# ESP8266.net
KiCad netlist of a schematic drawn in Altium Designer
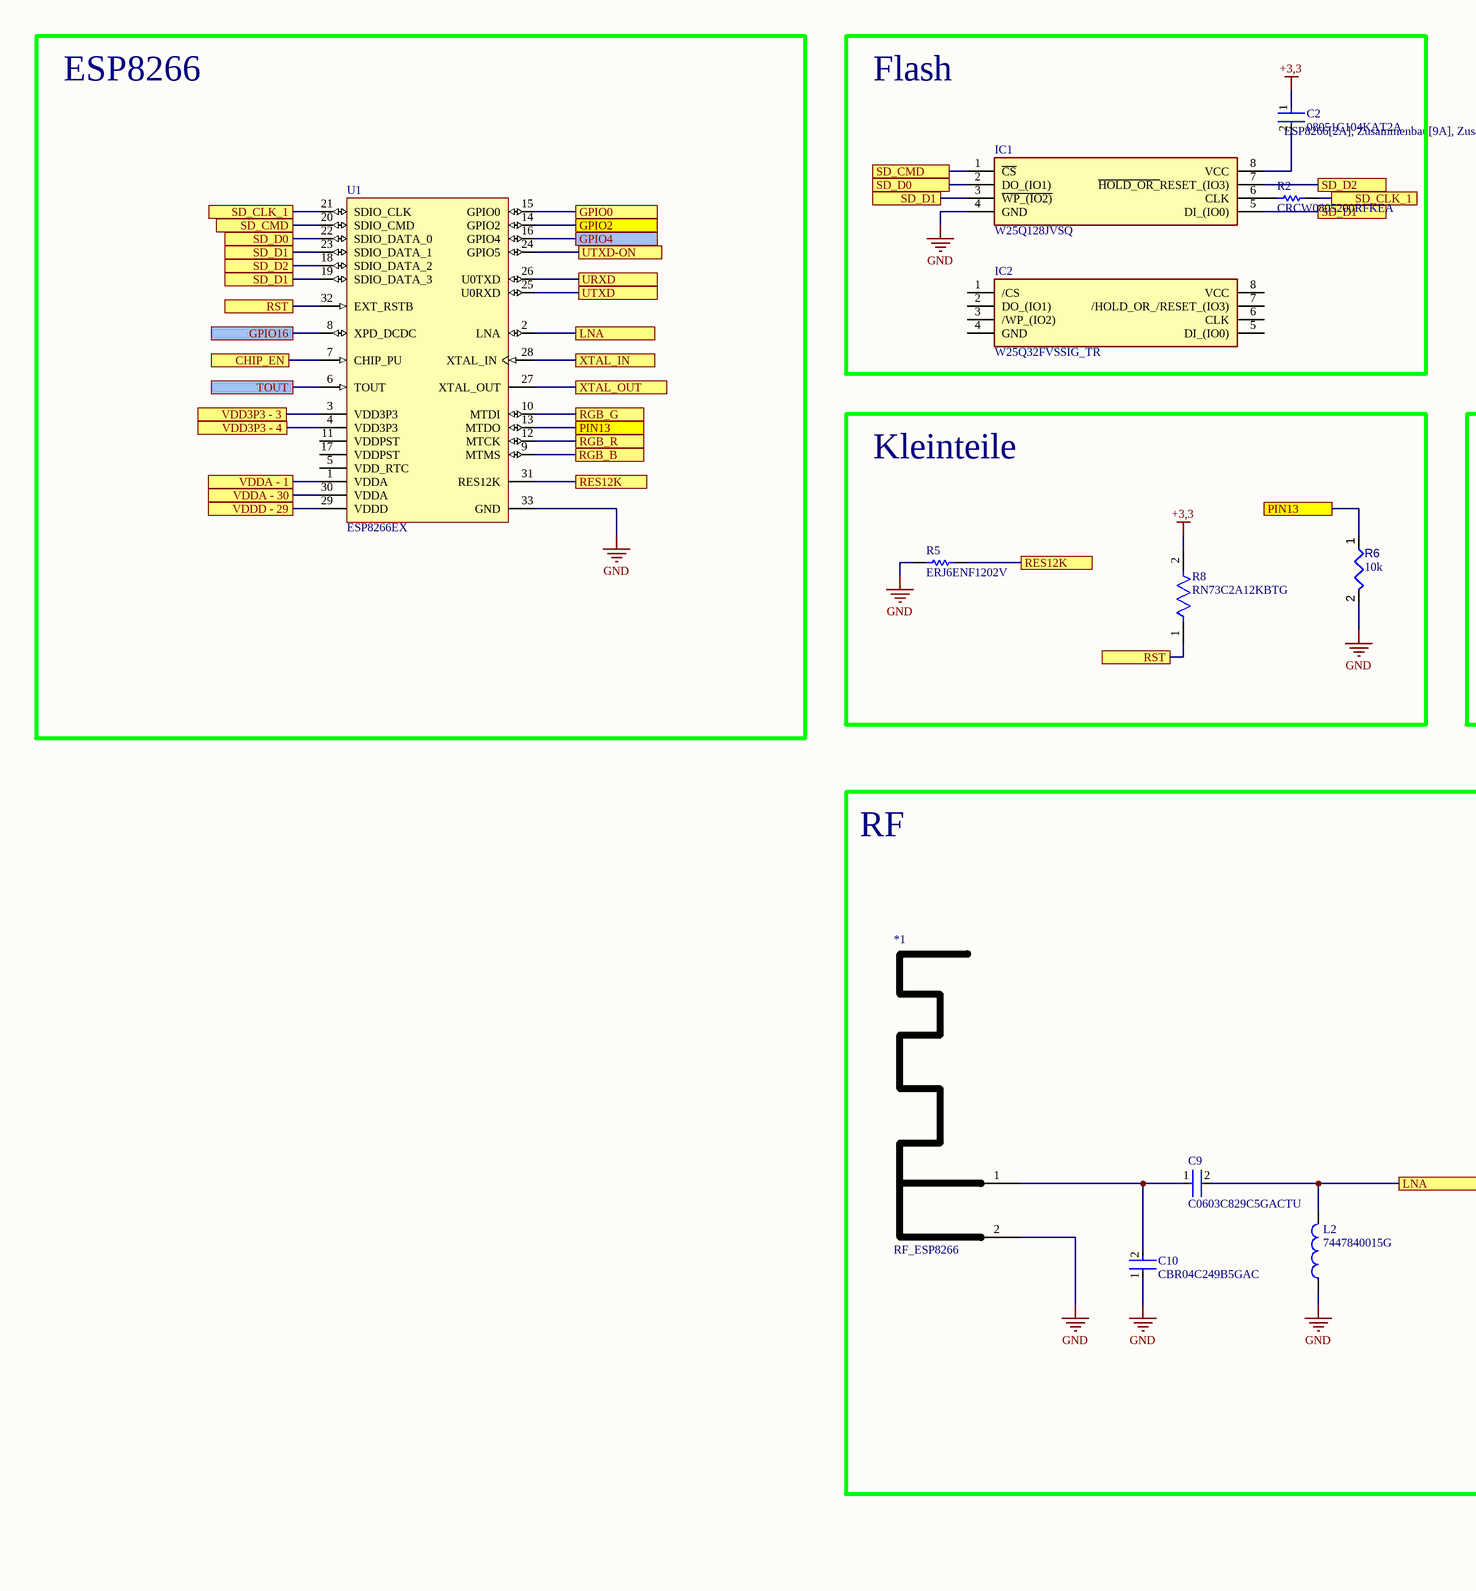
[diagram p0: ESP8266.SchDoc, left]
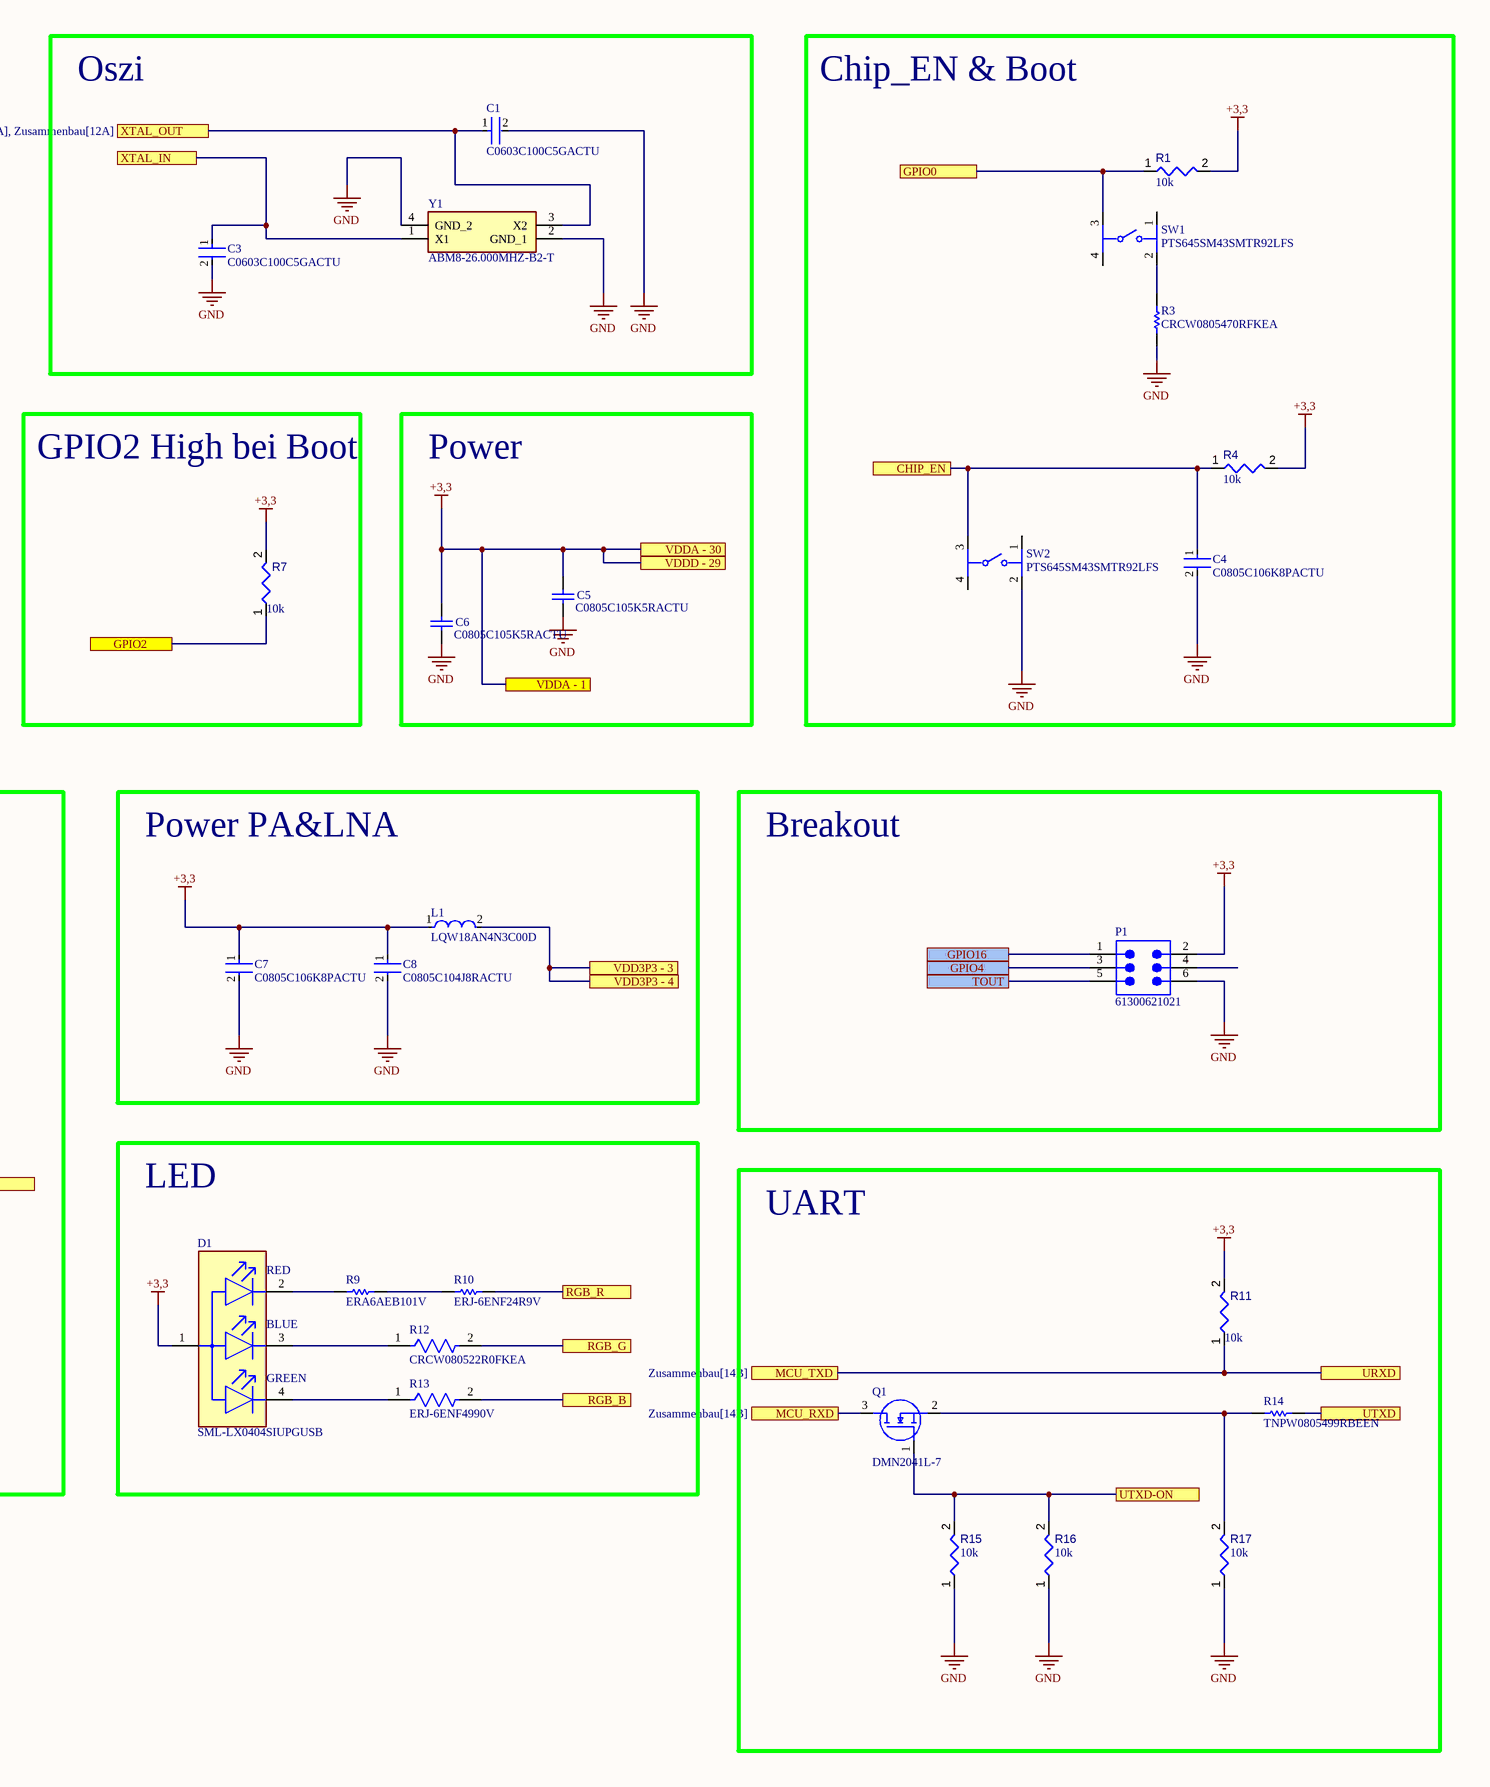
[diagram p1: ESP8266.SchDoc, right]

(export (version "E")
  (design (tool "Eeschema 10.0.6"))
  (components
    (comp (ref "*1")
      (value "RF_ESP8266")
      (footprint "PCBComponent_1")
      (libsource (lib "Stefan Hörtnagl") (part "Component_1"))
    )
    (comp (ref "C1")
      (value "C0603C100C5GACTU")
      (footprint "FP-C0603C-CF-MFG")
      (description "CAP CER 10PF 50V NP0 0603")
      (fields (field (name "MANUFACTURER") "KEMET") (field (name "TOLERANCE") "0.25 pF"))
      (libsource (lib "Altium Content Vault") (part "b4654b650e69147ec39a6b967a45e02"))
    )
    (comp (ref "C2")
      (value "08051C104KAT2A")
      (footprint "FP-0805-L_2_01_0_2-W_1_25-IPC_B")
      (description "General Purpose Ceramic Capacitor, 0805, 100nF, 10%, X7R, 15%, 100V")
      (fields (field (name "VOLTAGE") "100V") (field (name "TOLERANCE") "10%"))
      (libsource (lib "Altium Content Vault") (part "b4654b650e69147ec39a6b967a45e02"))
    )
    (comp (ref "C3")
      (value "C0603C100C5GACTU")
      (footprint "FP-C0603C-CF-MFG")
      (description "CAP CER 10PF 50V NP0 0603")
      (fields (field (name "MANUFACTURER") "KEMET") (field (name "TOLERANCE") "0.25 pF"))
      (libsource (lib "Altium Content Vault") (part "b4654b650e69147ec39a6b967a45e02"))
    )
    (comp (ref "C4")
      (value "C0805C106K8PACTU")
      (footprint "FP-C0805C-DG-MFG")
      (description "CAP CER 10UF 10V X5R 0805")
      (fields (field (name "TOLERANCE") "10%") (field (name "MANUFACTURER") "Kemet"))
      (libsource (lib "Altium Content Vault") (part "11868f565c42a9108669ba33697ecf6"))
    )
    (comp (ref "C5")
      (value "C0805C105K5RACTU")
      (footprint "CAPC2013X140X50ML20T25")
      (fields (field (name "MANUFACTURER") "Kemet"))
      (libsource (lib "Altium Content Vault") (part "CAP"))
    )
    (comp (ref "C6")
      (value "C0805C105K5RACTU")
      (footprint "CAPC2013X140X50ML20T25")
      (fields (field (name "MANUFACTURER") "Kemet"))
      (libsource (lib "Altium Content Vault") (part "CAP"))
    )
    (comp (ref "C7")
      (value "C0805C106K8PACTU")
      (footprint "FP-C0805C-DG-MFG")
      (description "CAP CER 10UF 10V X5R 0805")
      (fields (field (name "TOLERANCE") "10%") (field (name "MANUFACTURER") "Kemet"))
      (libsource (lib "Altium Content Vault") (part "11868f565c42a9108669ba33697ecf6"))
    )
    (comp (ref "C8")
      (value "C0805C104J8RACTU")
      (footprint "FP-C0805C-DN-MFG")
      (description "CAP CER 0.1UF 10V 5% X7R 0805")
      (fields (field (name "MANUFACTURER") "KEMET") (field (name "TOLERANCE") "0.05"))
      (libsource (lib "Altium Content Vault") (part "b4654b650e69147ec39a6b967a45e02"))
    )
    (comp (ref "C9")
      (value "C0603C829C5GACTU")
      (footprint "FP-C0603C-CF-MFG")
      (description "CAP CER 8.2PF 50V NP0 0603")
      (fields
        (field (name "OCTOPART") "https://octopart.com/c0603c829c5gactu-kemet-8375751")
        (field (name "TOLERANCE") "0.25 pF")
      )
      (libsource (lib "Altium Content Vault") (part "b4654b650e69147ec39a6b967a45e02"))
    )
    (comp (ref "C10")
      (value "CBR04C249B5GAC")
      (footprint "FP-CBR04C-MFG")
      (description "CBR0402 2.4 pF 30ppm/°C 0.1 pF C0G 50 V")
      (fields
        (field (name "OCTOPART") "https://octopart.com/cbr04c249b5gac-kemet-75200062")
        (field (name "MANUFACTURER") "KEMET")
      )
      (libsource (lib "Altium Content Vault") (part "236180d848d6139a670b325ea6854c9"))
    )
    (comp (ref "D1")
      (value "SML-LX0404SIUPGUSB")
      (footprint "FP-SML-LX0404SIUPGUSB-MFG")
      (description "LED RGB CLEAR SMD")
      (libsource (lib "Altium Content Vault") (part "2e8871f6955a40d35a6a753e53ead77"))
    )
    (comp (ref "IC1")
      (value "W25Q128JVSQ")
      (footprint "SamacSys:SOIC127P790X216-8N")
      (description "Integrated Circuit")
      (libsource (lib "*") (part "W25Q128JVSQ"))
    )
    (comp (ref "IC2")
      (value "W25Q32FVSSIG_TR")
      (footprint "SamacSys:SOIC127P790X216-8N")
      (description "Integrated Circuit")
      (fields (field (name "MANUFACTURER_PART_NUMBER") "W25Q32FVSSIG TR"))
      (libsource (lib "*") (part "W25Q32FVSSIG_TR"))
    )
    (comp (ref "L1")
      (value "LQW18AN4N3C00D")
      (footprint "FP-LQW18AN_00-MFG")
      (description "Wire Wound RF Inductor 4.3nH ±0.2nH 850mA 0.059Ω 0603 (1608)")
      (libsource (lib "Altium Content Vault") (part "725321dda6339637d4d059423bc1c3c"))
    )
    (comp (ref "L2")
      (value "7447840015G")
      (footprint "WE-MK_0402_L1W0.5H0.5")
      (description "7447840015G Multilayer Inductor, 1.5Nh, 0.3A, 0402 Rohs Compliant: Yes")
      (libsource (lib "Altium Content Vault") (part "Inductor - 1"))
    )
    (comp (ref "P1")
      (value "61300621021")
      (footprint "61300621021")
      (libsource (lib "Altium Content Vault") (part "Header_Male_2R_06P"))
    )
    (comp (ref "Q1")
      (value "DMN2041L-7")
      (footprint "SamacSys:SOT96P240X110-3N")
      (description "MOSFET (N-Channel)")
      (fields (field (name "MOUSER PART NUMBER") "621-DMN2041L-7"))
      (libsource (lib "*") (part "DMN2041L-7"))
    )
    (comp (ref "R1")
      (value "10k")
      (footprint "RESC2013X50X35ML15T15")
      (description "Chip Resistor, 10 KOhm, +/- 1%, 125 mW, -55 to 155 degC, 0805 (2012 Metric)")
      (fields (field (name "TOLERANCE") "1%") (field (name "POWER") "125mW"))
      (libsource (lib "Stefan Hörtnagl") (part "RES-2"))
    )
    (comp (ref "R2")
      (value "CRCW0805200RFKEA")
      (footprint "RESC2013X50X30NL20T20")
      (fields (field (name "MANUFACTURER") "Vishay Dale"))
      (libsource (lib "Altium Content Vault") (part "RES"))
    )
    (comp (ref "R3")
      (value "CRCW0805470RFKEA")
      (footprint "RESC2013X50X30LL20T20")
      (fields (field (name "MANUFACTURER") "Vishay Dale"))
      (libsource (lib "Altium Content Vault") (part "RES"))
    )
    (comp (ref "R4")
      (value "10k")
      (footprint "RESC2013X50X35ML15T15")
      (description "Chip Resistor, 10 KOhm, +/- 1%, 125 mW, -55 to 155 degC, 0805 (2012 Metric)")
      (fields (field (name "TOLERANCE") "1%") (field (name "POWER") "125mW"))
      (libsource (lib "Stefan Hörtnagl") (part "RES-2"))
    )
    (comp (ref "R5")
      (value "ERJ6ENF1202V")
      (footprint "RESC2013X70X40ML20T20")
      (fields (field (name "MANUFACTURER") "Panasonic"))
      (libsource (lib "Altium Content Vault") (part "RES"))
    )
    (comp (ref "R6")
      (value "10k")
      (footprint "RESC2013X50X35ML15T15")
      (description "Chip Resistor, 10 KOhm, +/- 1%, 125 mW, -55 to 155 degC, 0805 (2012 Metric)")
      (fields (field (name "TOLERANCE") "1%") (field (name "POWER") "125mW"))
      (libsource (lib "Stefan Hörtnagl") (part "RES-2"))
    )
    (comp (ref "R7")
      (value "10k")
      (footprint "RESC2013X50X35ML15T15")
      (description "Chip Resistor, 10 KOhm, +/- 1%, 125 mW, -55 to 155 degC, 0805 (2012 Metric)")
      (fields (field (name "TOLERANCE") "1%") (field (name "POWER") "125mW"))
      (libsource (lib "Stefan Hörtnagl") (part "RES-2"))
    )
    (comp (ref "R8")
      (value "RN73C2A12KBTG")
      (footprint "FP-RN732A-MFG")
      (description "SMD Chip Resistor, Thin Film, 12KΩ, 100 V, 0805 [2012 Metric], 100 mW, 0.1%, RN73 Series")
      (fields (field (name "TOLERANCE") "0.1%") (field (name "MANUFACTURER") "TE Connectivity"))
      (libsource (lib "Altium Content Vault") (part "1029c3af85768c4190bb7ad29bc67b5"))
    )
    (comp (ref "R9")
      (value "ERA6AEB101V")
      (footprint "RESC2013X60X40ML20T25")
      (fields (field (name "MANUFACTURER") "Panasonic"))
      (libsource (lib "Altium Content Vault") (part "RES"))
    )
    (comp (ref "R10")
      (value "ERJ-6ENF24R9V")
      (footprint "RESC2013X70X40ML20T20")
      (fields (field (name "MANUFACTURER") "Panasonic"))
      (libsource (lib "Altium Content Vault") (part "RES"))
    )
    (comp (ref "R11")
      (value "10k")
      (footprint "RESC2013X50X35ML15T15")
      (description "Chip Resistor, 10 KOhm, +/- 1%, 125 mW, -55 to 155 degC, 0805 (2012 Metric)")
      (fields (field (name "TOLERANCE") "1%") (field (name "POWER") "125mW"))
      (libsource (lib "Stefan Hörtnagl") (part "RES-2"))
    )
    (comp (ref "R12")
      (value "CRCW080522R0FKEA")
      (footprint "FP-CRCW0805-e3-IPC_C")
      (description "RES Thick Film, 22Ω, 1%, 0.125W, 100ppm/°C, 0805")
      (fields (field (name "TOLERANCE") "1%"))
      (libsource (lib "Altium Content Vault") (part "1029c3af85768c4190bb7ad29bc67b5"))
    )
    (comp (ref "R13")
      (value "ERJ-6ENF4990V")
      (footprint "FP-ERJ6EN-IPC_B")
      (description "RES SMD 499 OHM 1% 1/8W 0805")
      (fields (field (name "TOLERANCE") "1%"))
      (libsource (lib "Altium Content Vault") (part "1029c3af85768c4190bb7ad29bc67b5"))
    )
    (comp (ref "R14")
      (value "TNPW0805499RBEEN")
      (footprint "RESC2013X55X40NL15T20")
      (fields (field (name "MANUFACTURER") "Vishay Dale"))
      (libsource (lib "Altium Content Vault") (part "RES"))
    )
    (comp (ref "R15")
      (value "10k")
      (footprint "RESC2013X50X35ML15T15")
      (description "Chip Resistor, 10 KOhm, +/- 1%, 125 mW, -55 to 155 degC, 0805 (2012 Metric)")
      (fields (field (name "TOLERANCE") "1%") (field (name "POWER") "125mW"))
      (libsource (lib "Stefan Hörtnagl") (part "RES-2"))
    )
    (comp (ref "R16")
      (value "10k")
      (footprint "RESC2013X50X35ML15T15")
      (description "Chip Resistor, 10 KOhm, +/- 1%, 125 mW, -55 to 155 degC, 0805 (2012 Metric)")
      (fields (field (name "TOLERANCE") "1%") (field (name "POWER") "125mW"))
      (libsource (lib "Stefan Hörtnagl") (part "RES-2"))
    )
    (comp (ref "R17")
      (value "10k")
      (footprint "RESC2013X50X35ML15T15")
      (description "Chip Resistor, 10 KOhm, +/- 1%, 125 mW, -55 to 155 degC, 0805 (2012 Metric)")
      (fields (field (name "TOLERANCE") "1%") (field (name "POWER") "125mW"))
      (libsource (lib "Stefan Hörtnagl") (part "RES-2"))
    )
    (comp (ref "SW1")
      (value "PTS645SM43SMTR92LFS")
      (footprint "FP-PTS645SM43SMTR92LFS-MFG")
      (description "SWITCH TACTILE SPST-NO 0.05A 12V")
      (libsource (lib "Altium Content Vault") (part "1adf0dd01260c80cf25a44bfd6b99ba"))
    )
    (comp (ref "SW2")
      (value "PTS645SM43SMTR92LFS")
      (footprint "FP-PTS645SM43SMTR92LFS-MFG")
      (description "SWITCH TACTILE SPST-NO 0.05A 12V")
      (libsource (lib "Altium Content Vault") (part "1adf0dd01260c80cf25a44bfd6b99ba"))
    )
    (comp (ref "U1")
      (value "ESP8266EX")
      (footprint "ESFS-QFN-32_L")
      (description "Low-Power, Highly-Integrated Wi-Fi Solution, 2.5 to 3.6 V, 80 mA, -40 to 125 degC, 32-Pin QFN")
      (fields (field (name "MANUFACTURER") "Espressif Systems"))
      (libsource (lib "Altium Content Vault") (part "ESFS-ESP8266EX-32"))
    )
    (comp (ref "Y1")
      (value "ABM8-26.000MHZ-B2-T")
      (footprint "SamacSys:ABM810000MHZ12D2W")
      (description "Crystal or Oscillator")
      (libsource (lib "*") (part "ABM8-26.000MHZ-B2-T"))
    )
  )
  (nets
    (net (code "1") (name "+3,3") (class "Default")
      (node (ref "C2") (pin "1") (pinfunction "1_1") (pintype "passive"))
      (node (ref "C5") (pin "2") (pinfunction "2_2") (pintype "passive"))
      (node (ref "C6") (pin "2") (pinfunction "2_2") (pintype "passive"))
      (node (ref "C7") (pin "1") (pinfunction "1_1") (pintype "passive"))
      (node (ref "C8") (pin "1") (pinfunction "1_1") (pintype "passive"))
      (node (ref "D1") (pin "1") (pinfunction "Common_Anode_1") (pintype "passive"))
      (node (ref "L1") (pin "1") (pinfunction "1_1") (pintype "passive"))
      (node (ref "P1") (pin "2") (pinfunction "2_2") (pintype "passive"))
      (node (ref "R1") (pin "2") (pinfunction "2_2") (pintype "passive"))
      (node (ref "R11") (pin "2") (pinfunction "2_2") (pintype "passive"))
      (node (ref "R4") (pin "2") (pinfunction "2_2") (pintype "passive"))
      (node (ref "R7") (pin "2") (pinfunction "2_2") (pintype "passive"))
      (node (ref "R8") (pin "2") (pinfunction "2_2") (pintype "passive"))
      (node (ref "U1") (pin "1") (pinfunction "VDDA_1") (pintype "power_in"))
      (node (ref "U1") (pin "29") (pinfunction "VDDD_29") (pintype "power_in"))
      (node (ref "U1") (pin "30") (pinfunction "VDDA_30") (pintype "power_in"))
    )
    (net (code "2") (name "/CHIP_EN") (class "Default")
      (node (ref "C4") (pin "1") (pinfunction "1_1") (pintype "passive"))
      (node (ref "R4") (pin "1") (pinfunction "1_1") (pintype "passive"))
      (node (ref "SW2") (pin "3") (pinfunction "3_3") (pintype "passive"))
      (node (ref "U1") (pin "7") (pinfunction "CHIP_PU_7") (pintype "input"))
    )
    (net (code "3") (name "/GPIO0") (class "Default")
      (node (ref "R1") (pin "1") (pinfunction "1_1") (pintype "passive"))
      (node (ref "SW1") (pin "3") (pinfunction "3_3") (pintype "passive"))
      (node (ref "U1") (pin "15") (pinfunction "GPIO0_15") (pintype "bidirectional"))
    )
    (net (code "4") (name "/GPIO2") (class "Default")
      (node (ref "R7") (pin "1") (pinfunction "1_1") (pintype "passive"))
      (node (ref "U1") (pin "14") (pinfunction "GPIO2_14") (pintype "bidirectional"))
    )
    (net (code "5") (name "/GPIO4") (class "Default")
      (node (ref "P1") (pin "3") (pinfunction "3_3") (pintype "passive"))
      (node (ref "U1") (pin "16") (pinfunction "GPIO4_16") (pintype "bidirectional"))
    )
    (net (code "6") (name "/GPIO16") (class "Default")
      (node (ref "P1") (pin "1") (pinfunction "1_1") (pintype "passive"))
      (node (ref "U1") (pin "8") (pinfunction "XPD_DCDC_8") (pintype "bidirectional"))
    )
    (net (code "7") (name "/LNA") (class "Default")
      (node (ref "C9") (pin "2") (pinfunction "2_2") (pintype "passive"))
      (node (ref "L2") (pin "2") (pinfunction "2_2") (pintype "passive"))
      (node (ref "U1") (pin "2") (pinfunction "LNA_2") (pintype "bidirectional"))
    )
    (net (code "8") (name "/MCU_RXD") (class "Default")
      (node (ref "Q1") (pin "3") (pinfunction "D_3") (pintype "passive"))
    )
    (net (code "9") (name "/MCU_TXD") (class "Default")
      (node (ref "R11") (pin "1") (pinfunction "1_1") (pintype "passive"))
      (node (ref "U1") (pin "26") (pinfunction "U0TXD_26") (pintype "bidirectional"))
    )
    (net (code "10") (name "/PIN13") (class "Default")
      (node (ref "R6") (pin "1") (pinfunction "1_1") (pintype "passive"))
      (node (ref "U1") (pin "13") (pinfunction "MTDO_13") (pintype "bidirectional"))
    )
    (net (code "11") (name "/RES12K") (class "Default")
      (node (ref "R5") (pin "2") (pinfunction "2_2") (pintype "passive"))
      (node (ref "U1") (pin "31") (pinfunction "RES12K_31") (pintype "passive"))
    )
    (net (code "12") (name "/RGB_B") (class "Default")
      (node (ref "R13") (pin "2") (pinfunction "2_2") (pintype "passive"))
      (node (ref "U1") (pin "9") (pinfunction "MTMS_9") (pintype "bidirectional"))
    )
    (net (code "13") (name "/RGB_G") (class "Default")
      (node (ref "R12") (pin "2") (pinfunction "2_2") (pintype "passive"))
      (node (ref "U1") (pin "10") (pinfunction "MTDI_10") (pintype "bidirectional"))
    )
    (net (code "14") (name "/RGB_R") (class "Default")
      (node (ref "R10") (pin "2") (pinfunction "2_2") (pintype "passive"))
      (node (ref "U1") (pin "12") (pinfunction "MTCK_12") (pintype "bidirectional"))
    )
    (net (code "15") (name "/RST") (class "Default")
      (node (ref "R8") (pin "1") (pinfunction "1_1") (pintype "passive"))
      (node (ref "U1") (pin "32") (pinfunction "EXT_RSTB_32") (pintype "input"))
    )
    (net (code "16") (name "/SD_CLK_1") (class "Default")
      (node (ref "R2") (pin "2") (pinfunction "2_2") (pintype "passive"))
      (node (ref "U1") (pin "21") (pinfunction "SDIO_CLK_21") (pintype "bidirectional"))
    )
    (net (code "17") (name "/SD_CMD") (class "Default")
      (node (ref "IC1") (pin "1") (pinfunction "~{CS}_1") (pintype "passive"))
      (node (ref "U1") (pin "20") (pinfunction "SDIO_CMD_20") (pintype "bidirectional"))
    )
    (net (code "18") (name "/SD_D0") (class "Default")
      (node (ref "IC1") (pin "2") (pinfunction "DO_(IO1)_2") (pintype "passive"))
      (node (ref "U1") (pin "22") (pinfunction "SDIO_DATA_0_22") (pintype "bidirectional"))
    )
    (net (code "19") (name "/SD_D1") (class "Default")
      (node (ref "IC1") (pin "3") (pinfunction "~{WP_(IO2)}_3") (pintype "passive"))
      (node (ref "IC1") (pin "5") (pinfunction "DI_(IO0)_5") (pintype "passive"))
      (node (ref "U1") (pin "19") (pinfunction "SDIO_DATA_3_19") (pintype "bidirectional"))
      (node (ref "U1") (pin "23") (pinfunction "SDIO_DATA_1_23") (pintype "bidirectional"))
    )
    (net (code "20") (name "/SD_D2") (class "Default")
      (node (ref "IC1") (pin "7") (pinfunction "~{HOLD_OR_}RESET_(IO3)_7") (pintype "passive"))
      (node (ref "U1") (pin "18") (pinfunction "SDIO_DATA_2_18") (pintype "bidirectional"))
    )
    (net (code "21") (name "/TOUT") (class "Default")
      (node (ref "P1") (pin "5") (pinfunction "5_5") (pintype "passive"))
      (node (ref "U1") (pin "6") (pinfunction "TOUT_6") (pintype "input"))
    )
    (net (code "22") (name "/UTXD") (class "Default")
      (node (ref "R14") (pin "2") (pinfunction "2_2") (pintype "passive"))
      (node (ref "U1") (pin "25") (pinfunction "U0RXD_25") (pintype "bidirectional"))
    )
    (net (code "23") (name "/UTXD-ON") (class "Default")
      (node (ref "Q1") (pin "1") (pinfunction "G_1") (pintype "passive"))
      (node (ref "R15") (pin "2") (pinfunction "2_2") (pintype "passive"))
      (node (ref "R16") (pin "2") (pinfunction "2_2") (pintype "passive"))
      (node (ref "U1") (pin "24") (pinfunction "GPIO5_24") (pintype "bidirectional"))
    )
    (net (code "24") (name "/VDD3P3 - 3") (class "Default")
      (node (ref "L1") (pin "2") (pinfunction "2_2") (pintype "passive"))
      (node (ref "U1") (pin "3") (pinfunction "VDD3P3_3") (pintype "power_in"))
      (node (ref "U1") (pin "4") (pinfunction "VDD3P3_4") (pintype "power_in"))
    )
    (net (code "25") (name "/XTAL_IN") (class "Default")
      (node (ref "C3") (pin "1") (pinfunction "1_1") (pintype "passive"))
      (node (ref "U1") (pin "28") (pinfunction "XTAL_IN_28") (pintype "input"))
      (node (ref "Y1") (pin "1") (pinfunction "X1_1") (pintype "passive"))
    )
    (net (code "26") (name "/XTAL_OUT") (class "Default")
      (node (ref "C1") (pin "1") (pinfunction "1_1") (pintype "passive"))
      (node (ref "U1") (pin "27") (pinfunction "XTAL_OUT_27") (pintype "passive"))
      (node (ref "Y1") (pin "3") (pinfunction "X2_3") (pintype "passive"))
    )
    (net (code "27") (name "GND") (class "Default")
      (node (ref "*1") (pin "2") (pinfunction "GND_2") (pintype "passive"))
      (node (ref "C1") (pin "2") (pinfunction "2_2") (pintype "passive"))
      (node (ref "C10") (pin "1") (pinfunction "1_1") (pintype "passive"))
      (node (ref "C3") (pin "2") (pinfunction "2_2") (pintype "passive"))
      (node (ref "C4") (pin "2") (pinfunction "2_2") (pintype "passive"))
      (node (ref "C5") (pin "1") (pinfunction "1_1") (pintype "passive"))
      (node (ref "C6") (pin "1") (pinfunction "1_1") (pintype "passive"))
      (node (ref "C7") (pin "2") (pinfunction "2_2") (pintype "passive"))
      (node (ref "C8") (pin "2") (pinfunction "2_2") (pintype "passive"))
      (node (ref "IC1") (pin "4") (pinfunction "GND_4") (pintype "passive"))
      (node (ref "L2") (pin "1") (pinfunction "1_1") (pintype "passive"))
      (node (ref "P1") (pin "6") (pinfunction "6_6") (pintype "passive"))
      (node (ref "R15") (pin "1") (pinfunction "1_1") (pintype "passive"))
      (node (ref "R16") (pin "1") (pinfunction "1_1") (pintype "passive"))
      (node (ref "R17") (pin "1") (pinfunction "1_1") (pintype "passive"))
      (node (ref "R3") (pin "1") (pinfunction "1_1") (pintype "passive"))
      (node (ref "R5") (pin "1") (pinfunction "1_1") (pintype "passive"))
      (node (ref "R6") (pin "2") (pinfunction "2_2") (pintype "passive"))
      (node (ref "SW2") (pin "2") (pinfunction "2_2") (pintype "passive"))
      (node (ref "U1") (pin "33") (pinfunction "GND_33") (pintype "power_in"))
      (node (ref "Y1") (pin "2") (pinfunction "GND_1_2") (pintype "passive"))
      (node (ref "Y1") (pin "4") (pinfunction "GND_2_4") (pintype "passive"))
    )
    (net (code "28") (name "Net-(*1-LNA)") (class "Default")
      (node (ref "*1") (pin "1") (pinfunction "LNA_1") (pintype "passive"))
      (node (ref "C10") (pin "2") (pinfunction "2_2") (pintype "passive"))
      (node (ref "C9") (pin "1") (pinfunction "1_1") (pintype "passive"))
    )
    (net (code "29") (name "Net-(D1-Blue_C)") (class "Default")
      (node (ref "D1") (pin "3") (pinfunction "Blue_C_3") (pintype "passive"))
      (node (ref "R12") (pin "1") (pinfunction "1_1") (pintype "passive"))
    )
    (net (code "30") (name "Net-(D1-Green_C)") (class "Default")
      (node (ref "D1") (pin "4") (pinfunction "Green_C_4") (pintype "passive"))
      (node (ref "R13") (pin "1") (pinfunction "1_1") (pintype "passive"))
    )
    (net (code "31") (name "Net-(D1-Red_C)") (class "Default")
      (node (ref "D1") (pin "2") (pinfunction "Red_C_2") (pintype "passive"))
      (node (ref "R9") (pin "1") (pinfunction "1_1") (pintype "passive"))
    )
    (net (code "32") (name "Net-(IC1-CLK)") (class "Default")
      (node (ref "IC1") (pin "6") (pinfunction "CLK_6") (pintype "passive"))
      (node (ref "R2") (pin "1") (pinfunction "1_1") (pintype "passive"))
    )
    (net (code "33") (name "Net-(IC1-VCC)") (class "Default")
      (node (ref "C2") (pin "2") (pinfunction "2_2") (pintype "passive"))
      (node (ref "IC1") (pin "8") (pinfunction "VCC_8") (pintype "passive"))
    )
    (net (code "34") (name "Net-(Q1-S)") (class "Default")
      (node (ref "Q1") (pin "2") (pinfunction "S_2") (pintype "passive"))
      (node (ref "R14") (pin "1") (pinfunction "1_1") (pintype "passive"))
      (node (ref "R17") (pin "2") (pinfunction "2_2") (pintype "passive"))
    )
    (net (code "35") (name "Net-(R3-Pad2)") (class "Default")
      (node (ref "R3") (pin "2") (pinfunction "2_2") (pintype "passive"))
      (node (ref "SW1") (pin "2") (pinfunction "2_2") (pintype "passive"))
    )
    (net (code "36") (name "Net-(R10-Pad1)") (class "Default")
      (node (ref "R10") (pin "1") (pinfunction "1_1") (pintype "passive"))
      (node (ref "R9") (pin "2") (pinfunction "2_2") (pintype "passive"))
    )
    (net (code "37") (name "unconnected-(IC2-CLK-Pad6)") (class "Default")
      (node (ref "IC2") (pin "6") (pinfunction "CLK_6") (pintype "passive"))
    )
    (net (code "38") (name "unconnected-(IC2-DI_(IO0)-Pad5)") (class "Default")
      (node (ref "IC2") (pin "5") (pinfunction "DI_(IO0)_5") (pintype "passive"))
    )
    (net (code "39") (name "unconnected-(IC2-DO_(IO1)-Pad2)") (class "Default")
      (node (ref "IC2") (pin "2") (pinfunction "DO_(IO1)_2") (pintype "passive"))
    )
    (net (code "40") (name "unconnected-(IC2-GND-Pad4)") (class "Default")
      (node (ref "IC2") (pin "4") (pinfunction "GND_4") (pintype "passive"))
    )
    (net (code "41") (name "unconnected-(IC2-VCC-Pad8)") (class "Default")
      (node (ref "IC2") (pin "8") (pinfunction "VCC_8") (pintype "passive"))
    )
    (net (code "42") (name "unconnected-(IC2-{slash}CS-Pad1)") (class "Default")
      (node (ref "IC2") (pin "1") (pinfunction "/CS_1") (pintype "passive"))
    )
    (net (code "43") (name "unconnected-(IC2-{slash}HOLD_OR_{slash}RESET_(IO3)-Pad7)") (class "Default")
      (node (ref "IC2") (pin "7") (pinfunction "/HOLD_OR_/RESET_(IO3)_7") (pintype "passive"))
    )
    (net (code "44") (name "unconnected-(IC2-{slash}WP_(IO2)-Pad3)") (class "Default")
      (node (ref "IC2") (pin "3") (pinfunction "/WP_(IO2)_3") (pintype "passive"))
    )
    (net (code "45") (name "unconnected-(P1-Pad4)") (class "Default")
      (node (ref "P1") (pin "4") (pinfunction "4_4") (pintype "passive"))
    )
    (net (code "46") (name "unconnected-(SW1-Pad1)") (class "Default")
      (node (ref "SW1") (pin "1") (pinfunction "1_1") (pintype "passive"))
    )
    (net (code "47") (name "unconnected-(SW1-Pad4)") (class "Default")
      (node (ref "SW1") (pin "4") (pinfunction "4_4") (pintype "passive"))
    )
    (net (code "48") (name "unconnected-(SW2-Pad1)") (class "Default")
      (node (ref "SW2") (pin "1") (pinfunction "1_1") (pintype "passive"))
    )
    (net (code "49") (name "unconnected-(SW2-Pad4)") (class "Default")
      (node (ref "SW2") (pin "4") (pinfunction "4_4") (pintype "passive"))
    )
    (net (code "50") (name "unconnected-(U1-VDDPST-Pad11)") (class "Default")
      (node (ref "U1") (pin "11") (pinfunction "VDDPST_11") (pintype "power_in"))
    )
    (net (code "51") (name "unconnected-(U1-VDDPST-Pad17)") (class "Default")
      (node (ref "U1") (pin "17") (pinfunction "VDDPST_17") (pintype "power_in"))
    )
    (net (code "52") (name "unconnected-(U1-VDD_RTC-Pad5)") (class "Default")
      (node (ref "U1") (pin "5") (pinfunction "VDD_RTC_5") (pintype "power_in"))
    )
  )
)
